# MCU.net
KiCad netlist of a schematic drawn in Altium Designer
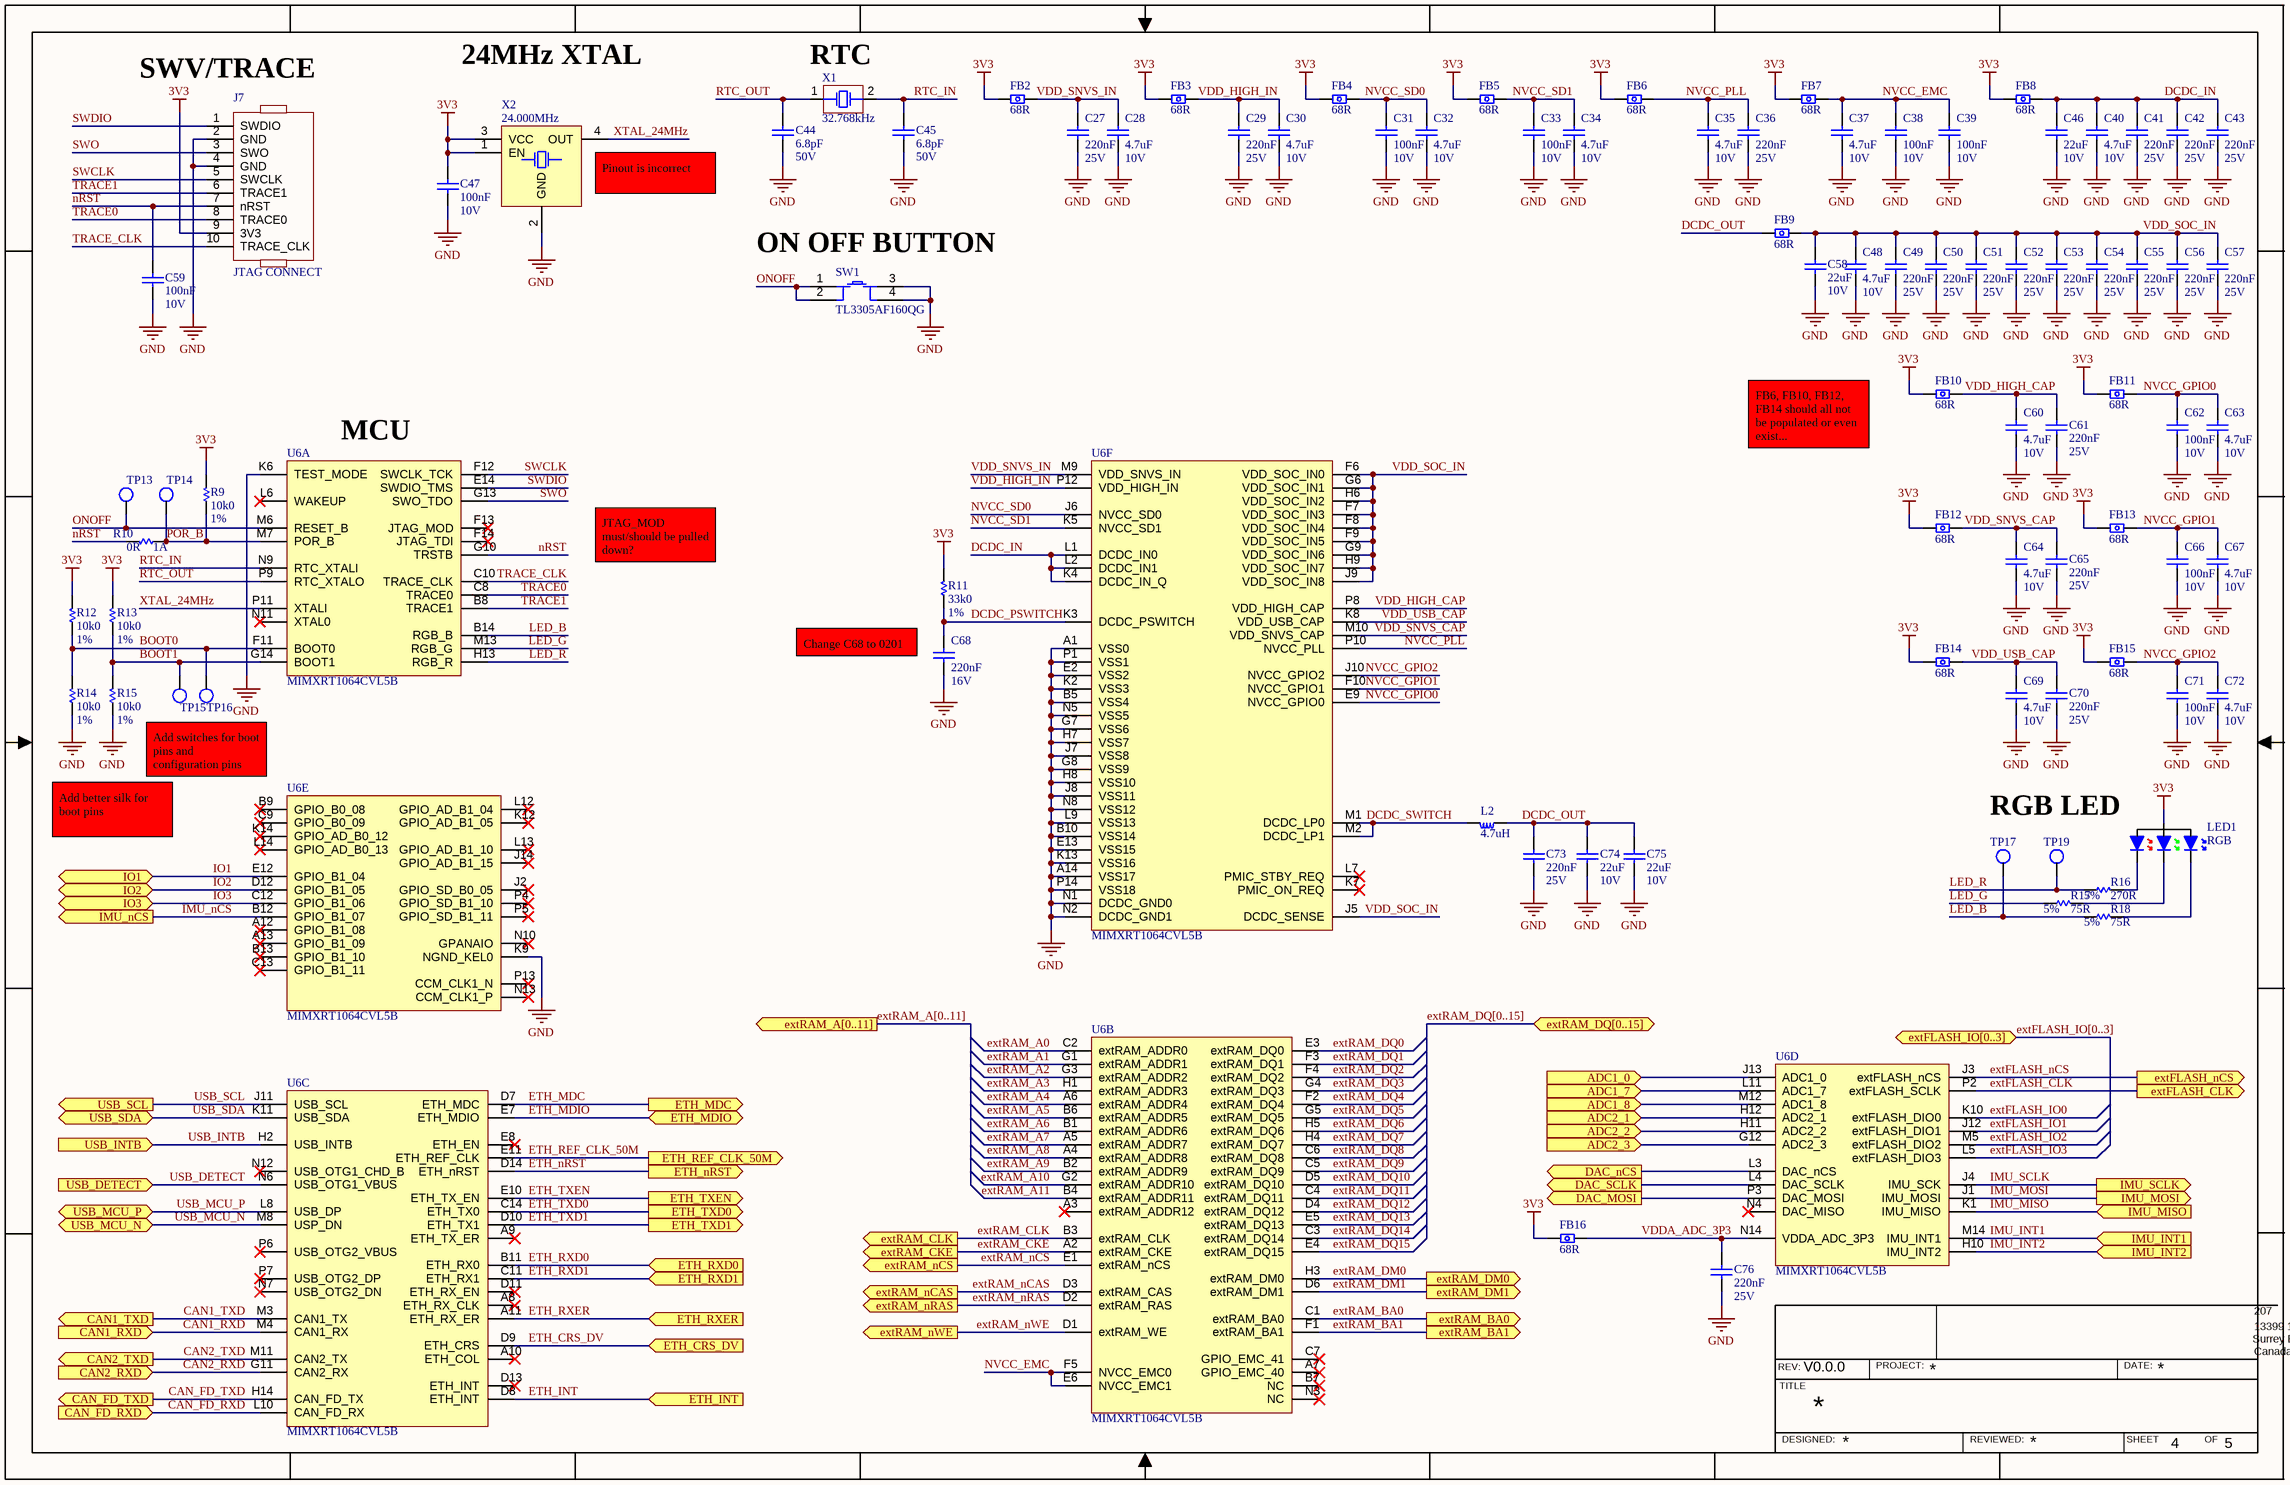
[diagram p0: MCU.SchDoc]

(export (version "E")
  (design (tool "Eeschema 10.0.6"))
  (components
    (comp (ref "C27")
      (value "220nF")
      (footprint "c0201")
      (description "0201 0.22 uF 25 V ±20% Tolerance X5R Surface Mount Multilayer Ceramic Capacitor")
      (fields (field (name "VOLTAGE") "25V"))
      (libsource (lib "MCU") (part "CAP CER 220nF 25V X5R 0201"))
    )
    (comp (ref "C28")
      (value "4.7uF")
      (footprint "C0402")
      (description "0402 10 V 4.7 uF ±20% Tolerance X5R Multilayer Ceramic Chip Capacitor")
      (fields
        (field (name "MANUFACTURER") "Murata")
        (field (name "MANUFACTURER PART NUMBER") "GRM155R61A475MEAAD")
        (field (name "VOLTAGE RATING") "10V")
      )
      (libsource (lib "MCU") (part "CAP CER 4.7uF 10V X5R 0402"))
    )
    (comp (ref "C29")
      (value "220nF")
      (footprint "c0201")
      (description "0201 0.22 uF 25 V ±20% Tolerance X5R Surface Mount Multilayer Ceramic Capacitor")
      (fields (field (name "VOLTAGE") "25V"))
      (libsource (lib "MCU") (part "CAP CER 220nF 25V X5R 0201"))
    )
    (comp (ref "C30")
      (value "4.7uF")
      (footprint "C0402")
      (description "0402 10 V 4.7 uF ±20% Tolerance X5R Multilayer Ceramic Chip Capacitor")
      (fields
        (field (name "MANUFACTURER") "Murata")
        (field (name "MANUFACTURER PART NUMBER") "GRM155R61A475MEAAD")
        (field (name "VOLTAGE RATING") "10V")
      )
      (libsource (lib "MCU") (part "CAP CER 4.7uF 10V X5R 0402"))
    )
    (comp (ref "C31")
      (value "100nF")
      (footprint "C0201")
      (description "CAP CER 0.1UF 10V X5R 0201")
      (fields (field (name "TOLERANCE") "20%") (field (name "VOLTAGE RATING") "10V"))
      (libsource (lib "MCU") (part "CAP CER 100nF 10V X5R 0201"))
    )
    (comp (ref "C32")
      (value "4.7uF")
      (footprint "C0402")
      (description "0402 10 V 4.7 uF ±20% Tolerance X5R Multilayer Ceramic Chip Capacitor")
      (fields
        (field (name "MANUFACTURER") "Murata")
        (field (name "MANUFACTURER PART NUMBER") "GRM155R61A475MEAAD")
        (field (name "VOLTAGE RATING") "10V")
      )
      (libsource (lib "MCU") (part "CAP CER 4.7uF 10V X5R 0402"))
    )
    (comp (ref "C33")
      (value "100nF")
      (footprint "C0201")
      (description "CAP CER 0.1UF 10V X5R 0201")
      (fields (field (name "TOLERANCE") "20%") (field (name "VOLTAGE RATING") "10V"))
      (libsource (lib "MCU") (part "CAP CER 100nF 10V X5R 0201"))
    )
    (comp (ref "C34")
      (value "4.7uF")
      (footprint "C0402")
      (description "0402 10 V 4.7 uF ±20% Tolerance X5R Multilayer Ceramic Chip Capacitor")
      (fields
        (field (name "MANUFACTURER") "Murata")
        (field (name "MANUFACTURER PART NUMBER") "GRM155R61A475MEAAD")
        (field (name "VOLTAGE RATING") "10V")
      )
      (libsource (lib "MCU") (part "CAP CER 4.7uF 10V X5R 0402"))
    )
    (comp (ref "C35")
      (value "4.7uF")
      (footprint "C0402")
      (description "0402 10 V 4.7 uF ±20% Tolerance X5R Multilayer Ceramic Chip Capacitor")
      (fields
        (field (name "MANUFACTURER") "Murata")
        (field (name "MANUFACTURER PART NUMBER") "GRM155R61A475MEAAD")
        (field (name "VOLTAGE RATING") "10V")
      )
      (libsource (lib "MCU") (part "CAP CER 4.7uF 10V X5R 0402"))
    )
    (comp (ref "C36")
      (value "220nF")
      (footprint "c0201")
      (description "0201 0.22 uF 25 V ±20% Tolerance X5R Surface Mount Multilayer Ceramic Capacitor")
      (fields (field (name "VOLTAGE") "25V"))
      (libsource (lib "MCU") (part "CAP CER 220nF 25V X5R 0201"))
    )
    (comp (ref "C37")
      (value "4.7uF")
      (footprint "C0402")
      (description "0402 10 V 4.7 uF ±20% Tolerance X5R Multilayer Ceramic Chip Capacitor")
      (fields
        (field (name "MANUFACTURER") "Murata")
        (field (name "MANUFACTURER PART NUMBER") "GRM155R61A475MEAAD")
        (field (name "VOLTAGE RATING") "10V")
      )
      (libsource (lib "MCU") (part "CAP CER 4.7uF 10V X5R 0402"))
    )
    (comp (ref "C38")
      (value "100nF")
      (footprint "C0201")
      (description "CAP CER 0.1UF 10V X5R 0201")
      (fields (field (name "TOLERANCE") "20%") (field (name "VOLTAGE RATING") "10V"))
      (libsource (lib "MCU") (part "CAP CER 100nF 10V X5R 0201"))
    )
    (comp (ref "C39")
      (value "100nF")
      (footprint "C0201")
      (description "CAP CER 0.1UF 10V X5R 0201")
      (fields (field (name "TOLERANCE") "20%") (field (name "VOLTAGE RATING") "10V"))
      (libsource (lib "MCU") (part "CAP CER 100nF 10V X5R 0201"))
    )
    (comp (ref "C40")
      (value "4.7uF")
      (footprint "C0402")
      (description "0402 10 V 4.7 uF ±20% Tolerance X5R Multilayer Ceramic Chip Capacitor")
      (fields
        (field (name "MANUFACTURER") "Murata")
        (field (name "MANUFACTURER PART NUMBER") "GRM155R61A475MEAAD")
        (field (name "VOLTAGE RATING") "10V")
      )
      (libsource (lib "MCU") (part "CAP CER 4.7uF 10V X5R 0402"))
    )
    (comp (ref "C41")
      (value "220nF")
      (footprint "c0201")
      (description "0201 0.22 uF 25 V ±20% Tolerance X5R Surface Mount Multilayer Ceramic Capacitor")
      (fields (field (name "VOLTAGE") "25V"))
      (libsource (lib "MCU") (part "CAP CER 220nF 25V X5R 0201"))
    )
    (comp (ref "C42")
      (value "220nF")
      (footprint "c0201")
      (description "0201 0.22 uF 25 V ±20% Tolerance X5R Surface Mount Multilayer Ceramic Capacitor")
      (fields (field (name "VOLTAGE") "25V"))
      (libsource (lib "MCU") (part "CAP CER 220nF 25V X5R 0201"))
    )
    (comp (ref "C43")
      (value "220nF")
      (footprint "c0201")
      (description "0201 0.22 uF 25 V ±20% Tolerance X5R Surface Mount Multilayer Ceramic Capacitor")
      (fields (field (name "VOLTAGE") "25V"))
      (libsource (lib "MCU") (part "CAP CER 220nF 25V X5R 0201"))
    )
    (comp (ref "C44")
      (value "6.8pF")
      (footprint "C0402")
      (description "Ceramic capacitor SMD-0402 6, 8pF /50V C0G# C +-0, 25pF%, Samsung, RoHS")
      (fields
        (field (name "MANUFACTURER") "Samsung")
        (field (name "MANUFACTURER PART NUMBER") "CL05C6R8CB5NNNC")
        (field (name "VOLTAGE") "50V")
      )
      (libsource (lib "Control_SchematicLib") (part "CAP CER 6.8pF 50V C0G 0402"))
    )
    (comp (ref "C45")
      (value "6.8pF")
      (footprint "C0402")
      (description "Ceramic capacitor SMD-0402 6, 8pF /50V C0G# C +-0, 25pF%, Samsung, RoHS")
      (fields
        (field (name "MANUFACTURER") "Samsung")
        (field (name "MANUFACTURER PART NUMBER") "CL05C6R8CB5NNNC")
        (field (name "VOLTAGE") "50V")
      )
      (libsource (lib "Control_SchematicLib") (part "CAP CER 6.8pF 50V C0G 0402"))
    )
    (comp (ref "C46")
      (value "22uF")
      (footprint "c0603")
      (description "0603 22 uF 10 V ±20% Tolerance X5R Multilayer Ceramic Chip Capacitor")
      (fields
        (field (name "MANUFACTURER") "Murata")
        (field (name "MANUFACTURER PART NUMBER") "GRM188R61A226ME15D")
        (field (name "VOLTAGE RATING") "10V")
      )
      (libsource (lib "MCU") (part "CAP CER 22uF 10V X5R 0603"))
    )
    (comp (ref "C47")
      (value "100nF")
      (footprint "C0201")
      (description "CAP CER 0.1UF 10V X5R 0201")
      (fields (field (name "TOLERANCE") "20%") (field (name "VOLTAGE RATING") "10V"))
      (libsource (lib "MCU") (part "CAP CER 100nF 10V X5R 0201"))
    )
    (comp (ref "C48")
      (value "4.7uF")
      (footprint "C0402")
      (description "0402 10 V 4.7 uF ±20% Tolerance X5R Multilayer Ceramic Chip Capacitor")
      (fields
        (field (name "MANUFACTURER") "Murata")
        (field (name "MANUFACTURER PART NUMBER") "GRM155R61A475MEAAD")
        (field (name "VOLTAGE RATING") "10V")
      )
      (libsource (lib "MCU") (part "CAP CER 4.7uF 10V X5R 0402"))
    )
    (comp (ref "C49")
      (value "220nF")
      (footprint "c0201")
      (description "0201 0.22 uF 25 V ±20% Tolerance X5R Surface Mount Multilayer Ceramic Capacitor")
      (fields (field (name "VOLTAGE") "25V"))
      (libsource (lib "MCU") (part "CAP CER 220nF 25V X5R 0201"))
    )
    (comp (ref "C50")
      (value "220nF")
      (footprint "c0201")
      (description "0201 0.22 uF 25 V ±20% Tolerance X5R Surface Mount Multilayer Ceramic Capacitor")
      (fields (field (name "VOLTAGE") "25V"))
      (libsource (lib "MCU") (part "CAP CER 220nF 25V X5R 0201"))
    )
    (comp (ref "C51")
      (value "220nF")
      (footprint "c0201")
      (description "0201 0.22 uF 25 V ±20% Tolerance X5R Surface Mount Multilayer Ceramic Capacitor")
      (fields (field (name "VOLTAGE") "25V"))
      (libsource (lib "MCU") (part "CAP CER 220nF 25V X5R 0201"))
    )
    (comp (ref "C52")
      (value "220nF")
      (footprint "c0201")
      (description "0201 0.22 uF 25 V ±20% Tolerance X5R Surface Mount Multilayer Ceramic Capacitor")
      (fields (field (name "VOLTAGE") "25V"))
      (libsource (lib "MCU") (part "CAP CER 220nF 25V X5R 0201"))
    )
    (comp (ref "C53")
      (value "220nF")
      (footprint "c0201")
      (description "0201 0.22 uF 25 V ±20% Tolerance X5R Surface Mount Multilayer Ceramic Capacitor")
      (fields (field (name "VOLTAGE") "25V"))
      (libsource (lib "MCU") (part "CAP CER 220nF 25V X5R 0201"))
    )
    (comp (ref "C54")
      (value "220nF")
      (footprint "c0201")
      (description "0201 0.22 uF 25 V ±20% Tolerance X5R Surface Mount Multilayer Ceramic Capacitor")
      (fields (field (name "VOLTAGE") "25V"))
      (libsource (lib "MCU") (part "CAP CER 220nF 25V X5R 0201"))
    )
    (comp (ref "C55")
      (value "220nF")
      (footprint "c0201")
      (description "0201 0.22 uF 25 V ±20% Tolerance X5R Surface Mount Multilayer Ceramic Capacitor")
      (fields (field (name "VOLTAGE") "25V"))
      (libsource (lib "MCU") (part "CAP CER 220nF 25V X5R 0201"))
    )
    (comp (ref "C56")
      (value "220nF")
      (footprint "c0201")
      (description "0201 0.22 uF 25 V ±20% Tolerance X5R Surface Mount Multilayer Ceramic Capacitor")
      (fields (field (name "VOLTAGE") "25V"))
      (libsource (lib "MCU") (part "CAP CER 220nF 25V X5R 0201"))
    )
    (comp (ref "C57")
      (value "220nF")
      (footprint "c0201")
      (description "0201 0.22 uF 25 V ±20% Tolerance X5R Surface Mount Multilayer Ceramic Capacitor")
      (fields (field (name "VOLTAGE") "25V"))
      (libsource (lib "MCU") (part "CAP CER 220nF 25V X5R 0201"))
    )
    (comp (ref "C58")
      (value "22uF")
      (footprint "c0603")
      (description "0603 22 uF 10 V ±20% Tolerance X5R Multilayer Ceramic Chip Capacitor")
      (fields
        (field (name "MANUFACTURER") "Murata")
        (field (name "MANUFACTURER PART NUMBER") "GRM188R61A226ME15D")
        (field (name "VOLTAGE RATING") "10V")
      )
      (libsource (lib "MCU") (part "CAP CER 22uF 10V X5R 0603"))
    )
    (comp (ref "C59")
      (value "100nF")
      (footprint "C0201")
      (description "CAP CER 0.1UF 10V X5R 0201")
      (fields (field (name "TOLERANCE") "20%") (field (name "VOLTAGE RATING") "10V"))
      (libsource (lib "MCU") (part "CAP CER 100nF 10V X5R 0201"))
    )
    (comp (ref "C60")
      (value "4.7uF")
      (footprint "C0402")
      (description "0402 10 V 4.7 uF ±20% Tolerance X5R Multilayer Ceramic Chip Capacitor")
      (fields
        (field (name "MANUFACTURER") "Murata")
        (field (name "MANUFACTURER PART NUMBER") "GRM155R61A475MEAAD")
        (field (name "VOLTAGE RATING") "10V")
      )
      (libsource (lib "MCU") (part "CAP CER 4.7uF 10V X5R 0402"))
    )
    (comp (ref "C61")
      (value "220nF")
      (footprint "c0201")
      (description "0201 0.22 uF 25 V ±20% Tolerance X5R Surface Mount Multilayer Ceramic Capacitor")
      (fields (field (name "VOLTAGE") "25V"))
      (libsource (lib "MCU") (part "CAP CER 220nF 25V X5R 0201"))
    )
    (comp (ref "C62")
      (value "100nF")
      (footprint "C0201")
      (description "CAP CER 0.1UF 10V X5R 0201")
      (fields (field (name "TOLERANCE") "20%") (field (name "VOLTAGE RATING") "10V"))
      (libsource (lib "MCU") (part "CAP CER 100nF 10V X5R 0201"))
    )
    (comp (ref "C63")
      (value "4.7uF")
      (footprint "C0402")
      (description "0402 10 V 4.7 uF ±20% Tolerance X5R Multilayer Ceramic Chip Capacitor")
      (fields
        (field (name "MANUFACTURER") "Murata")
        (field (name "MANUFACTURER PART NUMBER") "GRM155R61A475MEAAD")
        (field (name "VOLTAGE RATING") "10V")
      )
      (libsource (lib "MCU") (part "CAP CER 4.7uF 10V X5R 0402"))
    )
    (comp (ref "C64")
      (value "4.7uF")
      (footprint "C0402")
      (description "0402 10 V 4.7 uF ±20% Tolerance X5R Multilayer Ceramic Chip Capacitor")
      (fields
        (field (name "MANUFACTURER") "Murata")
        (field (name "MANUFACTURER PART NUMBER") "GRM155R61A475MEAAD")
        (field (name "VOLTAGE RATING") "10V")
      )
      (libsource (lib "MCU") (part "CAP CER 4.7uF 10V X5R 0402"))
    )
    (comp (ref "C65")
      (value "220nF")
      (footprint "c0201")
      (description "0201 0.22 uF 25 V ±20% Tolerance X5R Surface Mount Multilayer Ceramic Capacitor")
      (fields (field (name "VOLTAGE") "25V"))
      (libsource (lib "MCU") (part "CAP CER 220nF 25V X5R 0201"))
    )
    (comp (ref "C66")
      (value "100nF")
      (footprint "C0201")
      (description "CAP CER 0.1UF 10V X5R 0201")
      (fields (field (name "TOLERANCE") "20%") (field (name "VOLTAGE RATING") "10V"))
      (libsource (lib "MCU") (part "CAP CER 100nF 10V X5R 0201"))
    )
    (comp (ref "C67")
      (value "4.7uF")
      (footprint "C0402")
      (description "0402 10 V 4.7 uF ±20% Tolerance X5R Multilayer Ceramic Chip Capacitor")
      (fields
        (field (name "MANUFACTURER") "Murata")
        (field (name "MANUFACTURER PART NUMBER") "GRM155R61A475MEAAD")
        (field (name "VOLTAGE RATING") "10V")
      )
      (libsource (lib "MCU") (part "CAP CER 4.7uF 10V X5R 0402"))
    )
    (comp (ref "C68")
      (value "220nF")
      (footprint "C0402")
      (description "CAP CER 0.22UF 16V X7R 0402")
      (fields
        (field (name "MANUFACTURER") "Samsung")
        (field (name "MANUFACTURER PART NUMBER") "CL05B224KO5NNNC")
        (field (name "VOLTAGE RATING") "16V")
      )
      (libsource (lib "MCU") (part "CAP CER 220nF 16V X7R 0402"))
    )
    (comp (ref "C69")
      (value "4.7uF")
      (footprint "C0402")
      (description "0402 10 V 4.7 uF ±20% Tolerance X5R Multilayer Ceramic Chip Capacitor")
      (fields
        (field (name "MANUFACTURER") "Murata")
        (field (name "MANUFACTURER PART NUMBER") "GRM155R61A475MEAAD")
        (field (name "VOLTAGE RATING") "10V")
      )
      (libsource (lib "MCU") (part "CAP CER 4.7uF 10V X5R 0402"))
    )
    (comp (ref "C70")
      (value "220nF")
      (footprint "c0201")
      (description "0201 0.22 uF 25 V ±20% Tolerance X5R Surface Mount Multilayer Ceramic Capacitor")
      (fields (field (name "VOLTAGE") "25V"))
      (libsource (lib "MCU") (part "CAP CER 220nF 25V X5R 0201"))
    )
    (comp (ref "C71")
      (value "100nF")
      (footprint "C0201")
      (description "CAP CER 0.1UF 10V X5R 0201")
      (fields (field (name "TOLERANCE") "20%") (field (name "VOLTAGE RATING") "10V"))
      (libsource (lib "MCU") (part "CAP CER 100nF 10V X5R 0201"))
    )
    (comp (ref "C72")
      (value "4.7uF")
      (footprint "C0402")
      (description "0402 10 V 4.7 uF ±20% Tolerance X5R Multilayer Ceramic Chip Capacitor")
      (fields
        (field (name "MANUFACTURER") "Murata")
        (field (name "MANUFACTURER PART NUMBER") "GRM155R61A475MEAAD")
        (field (name "VOLTAGE RATING") "10V")
      )
      (libsource (lib "MCU") (part "CAP CER 4.7uF 10V X5R 0402"))
    )
    (comp (ref "C73")
      (value "220nF")
      (footprint "c0201")
      (description "0201 0.22 uF 25 V ±20% Tolerance X5R Surface Mount Multilayer Ceramic Capacitor")
      (fields (field (name "VOLTAGE") "25V"))
      (libsource (lib "MCU") (part "CAP CER 220nF 25V X5R 0201"))
    )
    (comp (ref "C74")
      (value "22uF")
      (footprint "c0603")
      (description "0603 22 uF 10 V ±20% Tolerance X5R Multilayer Ceramic Chip Capacitor")
      (fields
        (field (name "MANUFACTURER") "Murata")
        (field (name "MANUFACTURER PART NUMBER") "GRM188R61A226ME15D")
        (field (name "VOLTAGE RATING") "10V")
      )
      (libsource (lib "MCU") (part "CAP CER 22uF 10V X5R 0603"))
    )
    (comp (ref "C75")
      (value "22uF")
      (footprint "c0603")
      (description "0603 22 uF 10 V ±20% Tolerance X5R Multilayer Ceramic Chip Capacitor")
      (fields
        (field (name "MANUFACTURER") "Murata")
        (field (name "MANUFACTURER PART NUMBER") "GRM188R61A226ME15D")
        (field (name "VOLTAGE RATING") "10V")
      )
      (libsource (lib "MCU") (part "CAP CER 22uF 10V X5R 0603"))
    )
    (comp (ref "C76")
      (value "220nF")
      (footprint "c0201")
      (description "0201 0.22 uF 25 V ±20% Tolerance X5R Surface Mount Multilayer Ceramic Capacitor")
      (fields (field (name "VOLTAGE") "25V"))
      (libsource (lib "MCU") (part "CAP CER 220nF 25V X5R 0201"))
    )
    (comp (ref "FB2")
      (value "68R")
      (footprint "FB0402")
      (description "Ferrite Beads Multi-Layer 68Ohm 25% 100MHz 400mA 310mOhm DCR 0402 T/R")
      (fields
        (field (name "MANUFACTURER") "Taiyo Yuden")
        (field (name "MANUFACTURER PART NUMBER") "BK1005LL680-T")
      )
      (libsource (lib "MCU") (part "FB 68R 400mA 310mR 0402"))
    )
    (comp (ref "FB3")
      (value "68R")
      (footprint "FB0402")
      (description "Ferrite Beads Multi-Layer 68Ohm 25% 100MHz 400mA 310mOhm DCR 0402 T/R")
      (fields
        (field (name "MANUFACTURER") "Taiyo Yuden")
        (field (name "MANUFACTURER PART NUMBER") "BK1005LL680-T")
      )
      (libsource (lib "MCU") (part "FB 68R 400mA 310mR 0402"))
    )
    (comp (ref "FB4")
      (value "68R")
      (footprint "FB0402")
      (description "Ferrite Beads Multi-Layer 68Ohm 25% 100MHz 400mA 310mOhm DCR 0402 T/R")
      (fields
        (field (name "MANUFACTURER") "Taiyo Yuden")
        (field (name "MANUFACTURER PART NUMBER") "BK1005LL680-T")
      )
      (libsource (lib "MCU") (part "FB 68R 400mA 310mR 0402"))
    )
    (comp (ref "FB5")
      (value "68R")
      (footprint "FB0402")
      (description "Ferrite Beads Multi-Layer 68Ohm 25% 100MHz 400mA 310mOhm DCR 0402 T/R")
      (fields
        (field (name "MANUFACTURER") "Taiyo Yuden")
        (field (name "MANUFACTURER PART NUMBER") "BK1005LL680-T")
      )
      (libsource (lib "MCU") (part "FB 68R 400mA 310mR 0402"))
    )
    (comp (ref "FB6")
      (value "68R")
      (footprint "FB0402")
      (description "Ferrite Beads Multi-Layer 68Ohm 25% 100MHz 400mA 310mOhm DCR 0402 T/R")
      (fields
        (field (name "MANUFACTURER") "Taiyo Yuden")
        (field (name "MANUFACTURER PART NUMBER") "BK1005LL680-T")
      )
      (libsource (lib "MCU") (part "FB 68R 400mA 310mR 0402"))
    )
    (comp (ref "FB7")
      (value "68R")
      (footprint "FB0402")
      (description "Ferrite Beads Multi-Layer 68Ohm 25% 100MHz 400mA 310mOhm DCR 0402 T/R")
      (fields
        (field (name "MANUFACTURER") "Taiyo Yuden")
        (field (name "MANUFACTURER PART NUMBER") "BK1005LL680-T")
      )
      (libsource (lib "MCU") (part "FB 68R 400mA 310mR 0402"))
    )
    (comp (ref "FB8")
      (value "68R")
      (footprint "FB0402")
      (description "Ferrite Beads Multi-Layer 68Ohm 25% 100MHz 400mA 310mOhm DCR 0402 T/R")
      (fields
        (field (name "MANUFACTURER") "Taiyo Yuden")
        (field (name "MANUFACTURER PART NUMBER") "BK1005LL680-T")
      )
      (libsource (lib "MCU") (part "FB 68R 400mA 310mR 0402"))
    )
    (comp (ref "FB9")
      (value "68R")
      (footprint "FB0402")
      (description "Ferrite Beads Multi-Layer 68Ohm 25% 100MHz 400mA 310mOhm DCR 0402 T/R")
      (fields
        (field (name "MANUFACTURER") "Taiyo Yuden")
        (field (name "MANUFACTURER PART NUMBER") "BK1005LL680-T")
      )
      (libsource (lib "MCU") (part "FB 68R 400mA 310mR 0402"))
    )
    (comp (ref "FB10")
      (value "68R")
      (footprint "FB0402")
      (description "Ferrite Beads Multi-Layer 68Ohm 25% 100MHz 400mA 310mOhm DCR 0402 T/R")
      (fields
        (field (name "MANUFACTURER") "Taiyo Yuden")
        (field (name "MANUFACTURER PART NUMBER") "BK1005LL680-T")
      )
      (libsource (lib "MCU") (part "FB 68R 400mA 310mR 0402"))
    )
    (comp (ref "FB11")
      (value "68R")
      (footprint "FB0402")
      (description "Ferrite Beads Multi-Layer 68Ohm 25% 100MHz 400mA 310mOhm DCR 0402 T/R")
      (fields
        (field (name "MANUFACTURER") "Taiyo Yuden")
        (field (name "MANUFACTURER PART NUMBER") "BK1005LL680-T")
      )
      (libsource (lib "MCU") (part "FB 68R 400mA 310mR 0402"))
    )
    (comp (ref "FB12")
      (value "68R")
      (footprint "FB0402")
      (description "Ferrite Beads Multi-Layer 68Ohm 25% 100MHz 400mA 310mOhm DCR 0402 T/R")
      (fields
        (field (name "MANUFACTURER") "Taiyo Yuden")
        (field (name "MANUFACTURER PART NUMBER") "BK1005LL680-T")
      )
      (libsource (lib "MCU") (part "FB 68R 400mA 310mR 0402"))
    )
    (comp (ref "FB13")
      (value "68R")
      (footprint "FB0402")
      (description "Ferrite Beads Multi-Layer 68Ohm 25% 100MHz 400mA 310mOhm DCR 0402 T/R")
      (fields
        (field (name "MANUFACTURER") "Taiyo Yuden")
        (field (name "MANUFACTURER PART NUMBER") "BK1005LL680-T")
      )
      (libsource (lib "MCU") (part "FB 68R 400mA 310mR 0402"))
    )
    (comp (ref "FB14")
      (value "68R")
      (footprint "FB0402")
      (description "Ferrite Beads Multi-Layer 68Ohm 25% 100MHz 400mA 310mOhm DCR 0402 T/R")
      (fields
        (field (name "MANUFACTURER") "Taiyo Yuden")
        (field (name "MANUFACTURER PART NUMBER") "BK1005LL680-T")
      )
      (libsource (lib "MCU") (part "FB 68R 400mA 310mR 0402"))
    )
    (comp (ref "FB15")
      (value "68R")
      (footprint "FB0402")
      (description "Ferrite Beads Multi-Layer 68Ohm 25% 100MHz 400mA 310mOhm DCR 0402 T/R")
      (fields
        (field (name "MANUFACTURER") "Taiyo Yuden")
        (field (name "MANUFACTURER PART NUMBER") "BK1005LL680-T")
      )
      (libsource (lib "MCU") (part "FB 68R 400mA 310mR 0402"))
    )
    (comp (ref "FB16")
      (value "68R")
      (footprint "FB0402")
      (description "Ferrite Beads Multi-Layer 68Ohm 25% 100MHz 400mA 310mOhm DCR 0402 T/R")
      (fields
        (field (name "MANUFACTURER") "Taiyo Yuden")
        (field (name "MANUFACTURER PART NUMBER") "BK1005LL680-T")
      )
      (libsource (lib "MCU") (part "FB 68R 400mA 310mR 0402"))
    )
    (comp (ref "J7")
      (value "JTAG CONNECT")
      (footprint "TAG_CONNECT_10PIN")
      (description "10 pin jtag tag connect")
      (libsource (lib "MCU") (part "CONN TAG CONNECT 10 SWV"))
    )
    (comp (ref "L2")
      (value "4.7uH")
      (footprint "INDP3030X12N")
      (description "Inductor Power Shielded Wirewound 4.7uH 20% 100KHz Ferrite 1.06A 0.156Ohm DCR 1212 T/R")
      (fields
        (field (name "MANUFACTURER") "Taiyo Yuden")
        (field (name "MANUFACTURER PART NUMBER") "NRH3012T4R7MN")
      )
      (libsource (lib "MCU") (part "IND 2.7uH 1A 156mR 3030 NRH3012T4R7MN"))
    )
    (comp (ref "LED1")
      (value "RGB")
      (footprint "LED RGB UHD1110-FKA-CL1A13R3Q1BBQFMF3")
      (fields
        (field (name "MANUFACTURER") "Cree")
        (field (name "MANUFACTURER PART NUMBER") "UHD1110-FKA-CL1A13R3Q1BBQFMF3")
      )
      (libsource (lib "Control_SchematicLib") (part "LED RGB 5mA UHD1110-FKA-CL1A13R3Q1BBQFMF3"))
    )
    (comp (ref "R9")
      (value "10k0")
      (footprint "r0402")
      (description "Res General Purpose Thick Film 0402 10K Ohm 1% 1/16W ±100ppm/°C Molded SMD Paper T/R")
      (fields
        (field (name "MANUFACTURER") "Yageo")
        (field (name "MANUFACTURER PART NUMBER") "RC0402FR-0710KL")
        (field (name "TOLERANCE") "1%")
      )
      (libsource (lib "MCU") (part "RES 10k0 1% 63mW 0402"))
    )
    (comp (ref "R10")
      (value "0R")
      (footprint "R0402")
      (description "GLOVE, POLYAMIDE, L/FREE, PU, SIZE 6 - More Details")
      (fields
        (field (name "MANUFACTURER") "Stackpole Electronics")
        (field (name "MANUFACTURER PART NUMBER") "RMCF0402ZT0R00")
        (field (name "CURRENT RATING") "1A")
      )
      (libsource (lib "MCU") (part "RES 0R 63mW 0402"))
    )
    (comp (ref "R11")
      (value "33k0")
      (footprint "r0402")
      (description "Res Thick Film 0402 33K Ohm 1% 0.063W(1/16W) ±100ppm/C Pad SMD T/R")
      (fields
        (field (name "MANUFACTURER") "Samsung")
        (field (name "MANUFACTURER PART NUMBER") "RC1005F333CS")
        (field (name "TOLERANCE") "1%")
      )
      (libsource (lib "MCU") (part "RES 33k0 1% 63mW 0402"))
    )
    (comp (ref "R12")
      (value "10k0")
      (footprint "r0402")
      (description "Res General Purpose Thick Film 0402 10K Ohm 1% 1/16W ±100ppm/°C Molded SMD Paper T/R")
      (fields
        (field (name "MANUFACTURER") "Yageo")
        (field (name "MANUFACTURER PART NUMBER") "RC0402FR-0710KL")
        (field (name "TOLERANCE") "1%")
      )
      (libsource (lib "MCU") (part "RES 10k0 1% 63mW 0402"))
    )
    (comp (ref "R13")
      (value "10k0")
      (footprint "r0402")
      (description "Res General Purpose Thick Film 0402 10K Ohm 1% 1/16W ±100ppm/°C Molded SMD Paper T/R")
      (fields
        (field (name "MANUFACTURER") "Yageo")
        (field (name "MANUFACTURER PART NUMBER") "RC0402FR-0710KL")
        (field (name "TOLERANCE") "1%")
      )
      (libsource (lib "MCU") (part "RES 10k0 1% 63mW 0402"))
    )
    (comp (ref "R14")
      (value "10k0")
      (footprint "r0402")
      (description "Res General Purpose Thick Film 0402 10K Ohm 1% 1/16W ±100ppm/°C Molded SMD Paper T/R")
      (fields
        (field (name "MANUFACTURER") "Yageo")
        (field (name "MANUFACTURER PART NUMBER") "RC0402FR-0710KL")
        (field (name "TOLERANCE") "1%")
      )
      (libsource (lib "MCU") (part "RES 10k0 1% 63mW 0402"))
    )
    (comp (ref "R15")
      (value "10k0")
      (footprint "r0402")
      (description "Res General Purpose Thick Film 0402 10K Ohm 1% 1/16W ±100ppm/°C Molded SMD Paper T/R")
      (fields
        (field (name "MANUFACTURER") "Yageo")
        (field (name "MANUFACTURER PART NUMBER") "RC0402FR-0710KL")
        (field (name "TOLERANCE") "1%")
      )
      (libsource (lib "MCU") (part "RES 10k0 1% 63mW 0402"))
    )
    (comp (ref "R16")
      (value "270R")
      (footprint "r0402")
      (description "Res Thick Film 0402 270 Ohm 5% 0.063W(1/16W) ±100ppm/C Pad SMD Automotive T/R")
      (fields
        (field (name "MANUFACTURER") "Yageo")
        (field (name "MANUFACTURER PART NUMBER") "AC0402JR-07270RL")
        (field (name "TOLERANCE") "5%")
      )
      (libsource (lib "Control_SchematicLib") (part "RES 270R 5% 63mW 0402"))
    )
    (comp (ref "R17")
      (value "75R")
      (footprint "R0402")
      (description "Res Thick Film 0402 75 Ohm 5% 0.063W(1/16W) ±100ppm/C Pad SMD Automotive T/R")
      (fields
        (field (name "MANUFACTURER") "Stackpole Electronics")
        (field (name "MANUFACTURER PART NUMBER") "RMCF0402JT75R0")
        (field (name "TOLERANCE") "5%")
      )
      (libsource (lib "Control_SchematicLib") (part "RES 75R 5% 63mW 0402"))
    )
    (comp (ref "R18")
      (value "75R")
      (footprint "R0402")
      (description "Res Thick Film 0402 75 Ohm 5% 0.063W(1/16W) ±100ppm/C Pad SMD Automotive T/R")
      (fields
        (field (name "MANUFACTURER") "Stackpole Electronics")
        (field (name "MANUFACTURER PART NUMBER") "RMCF0402JT75R0")
        (field (name "TOLERANCE") "5%")
      )
      (libsource (lib "Control_SchematicLib") (part "RES 75R 5% 63mW 0402"))
    )
    (comp (ref "SW1")
      (value "TL3305AF160QG")
      (footprint "MECH PB TL3305A")
      (description "TL3305A Series SPST 12 V 4.5 x 4.5 mm 160 gf Top Actuated SMT Tactile Switch")
      (fields (field (name "MANUFACTURER") "E-Switch"))
      (libsource (lib "MCU") (part "MECH PB SPST TL3305AF160QG"))
    )
    (comp (ref "TP13")
      (value "1mm")
      (footprint "TESTPOINT_SMT")
      (description "SMT testpoint")
      (libsource (lib "DClassAmp_Symbol") (part "TP 1mm"))
    )
    (comp (ref "TP14")
      (value "1mm")
      (footprint "TESTPOINT_SMT")
      (description "SMT testpoint")
      (libsource (lib "DClassAmp_Symbol") (part "TP 1mm"))
    )
    (comp (ref "TP15")
      (value "1mm")
      (footprint "TESTPOINT_SMT")
      (description "SMT testpoint")
      (libsource (lib "DClassAmp_Symbol") (part "TP 1mm"))
    )
    (comp (ref "TP16")
      (value "1mm")
      (footprint "TESTPOINT_SMT")
      (description "SMT testpoint")
      (libsource (lib "DClassAmp_Symbol") (part "TP 1mm"))
    )
    (comp (ref "TP17")
      (value "1mm")
      (footprint "TESTPOINT_SMT")
      (description "SMT testpoint")
      (libsource (lib "DClassAmp_Symbol") (part "TP 1mm"))
    )
    (comp (ref "TP19")
      (value "1mm")
      (footprint "TESTPOINT_SMT")
      (description "SMT testpoint")
      (libsource (lib "DClassAmp_Symbol") (part "TP 1mm"))
    )
    (comp (ref "U6")
      (value "MIMXRT1064CVL5B")
      (footprint "BGA196C65P14X14_1000X1000X143")
      (description "i.MXRT1064 USB Fix 10 / TRAY TRAY MULTIPLE DP BAKEABLE RoHS Compliant: Yes")
      (fields (field (name "MANUFACTURER") "NXP Semiconductors"))
      (libsource (lib "MCU") (part "IC MCU 600MHz LaserDriver MIMXRT1064CVL5B"))
    )
    (comp (ref "X1")
      (value "32.768kHz")
      (footprint "XTAL 3.2x1.5mm")
      (description "Crystal 0.032768MHz ±20ppm (Tol) 12.5pF Flexural 70000Ohm 2-Pin Ultra Mini-CSMD T/R")
      (fields
        (field (name "MANUFACTURER") "ECS International")
        (field (name "MANUFACTURER PART NUMBER") "ECS-.327-12.5-34B-TR")
      )
      (libsource (lib "Control_SchematicLib") (part "XTAL 32.768kHz 20ppm 12.5pF 3.2x1.5mm"))
    )
    (comp (ref "X2")
      (value "24.000MHz")
      (footprint "XTAL FA-238V 3.2x2.5mm")
      (description "Oscillator MEMS 24MHz ±50ppm (Stability) 15pF LVCMOS 55% 3.3V Automotive 4-Pin QFN SMD T/R")
      (fields
        (field (name "MANUFACTURER") "Abracon")
        (field (name "MANUFACTURER PART NUMBER") "ASEM1-24.000MHZ-LC-T")
      )
      (libsource (lib "MCU") (part "XTAL OSC MEMS 24MHz 15pF ASEM1-24.000MHZ-LC-T"))
    )
  )
  (nets
    (net (code "1") (name "/ADC1_0") (class "Default")
      (node (ref "U6") (pin "J13") (pinfunction "ADC1_0_J13") (pintype "passive"))
    )
    (net (code "2") (name "/ADC1_7") (class "Default")
      (node (ref "U6") (pin "L11") (pinfunction "ADC1_7_L11") (pintype "passive"))
    )
    (net (code "3") (name "/ADC1_8") (class "Default")
      (node (ref "U6") (pin "M12") (pinfunction "ADC1_8_M12") (pintype "passive"))
    )
    (net (code "4") (name "/ADC2_1") (class "Default")
      (node (ref "U6") (pin "H12") (pinfunction "ADC2_1_H12") (pintype "passive"))
    )
    (net (code "5") (name "/ADC2_2") (class "Default")
      (node (ref "U6") (pin "H11") (pinfunction "ADC2_2_H11") (pintype "passive"))
    )
    (net (code "6") (name "/ADC2_3") (class "Default")
      (node (ref "U6") (pin "G12") (pinfunction "ADC2_3_G12") (pintype "passive"))
    )
    (net (code "7") (name "/BOOT0") (class "Default")
      (node (ref "R12") (pin "1") (pinfunction "1_1") (pintype "passive"))
      (node (ref "R14") (pin "2") (pinfunction "2_2") (pintype "passive"))
      (node (ref "TP16") (pin "1") (pinfunction "1_1") (pintype "passive"))
      (node (ref "U6") (pin "F11") (pinfunction "BOOT0_F11") (pintype "passive"))
    )
    (net (code "8") (name "/BOOT1") (class "Default")
      (node (ref "R13") (pin "1") (pinfunction "1_1") (pintype "passive"))
      (node (ref "R15") (pin "2") (pinfunction "2_2") (pintype "passive"))
      (node (ref "TP15") (pin "1") (pinfunction "1_1") (pintype "passive"))
      (node (ref "U6") (pin "G14") (pinfunction "BOOT1_G14") (pintype "passive"))
    )
    (net (code "9") (name "/CAN1_RXD") (class "Default")
      (node (ref "U6") (pin "M4") (pinfunction "CAN1_RX_M4") (pintype "passive"))
    )
    (net (code "10") (name "/CAN1_TXD") (class "Default")
      (node (ref "U6") (pin "M3") (pinfunction "CAN1_TX_M3") (pintype "passive"))
    )
    (net (code "11") (name "/CAN2_RXD") (class "Default")
      (node (ref "U6") (pin "G11") (pinfunction "CAN2_RX_G11") (pintype "passive"))
    )
    (net (code "12") (name "/CAN2_TXD") (class "Default")
      (node (ref "U6") (pin "M11") (pinfunction "CAN2_TX_M11") (pintype "passive"))
    )
    (net (code "13") (name "/CAN_FD_RXD") (class "Default")
      (node (ref "U6") (pin "L10") (pinfunction "CAN_FD_RX_L10") (pintype "passive"))
    )
    (net (code "14") (name "/CAN_FD_TXD") (class "Default")
      (node (ref "U6") (pin "H14") (pinfunction "CAN_FD_TX_H14") (pintype "passive"))
    )
    (net (code "15") (name "/DAC_MOSI") (class "Default")
      (node (ref "U6") (pin "P3") (pinfunction "DAC_MOSI_P3") (pintype "passive"))
    )
    (net (code "16") (name "/DAC_SCLK") (class "Default")
      (node (ref "U6") (pin "L4") (pinfunction "DAC_SCLK_L4") (pintype "passive"))
    )
    (net (code "17") (name "/DAC_nCS") (class "Default")
      (node (ref "U6") (pin "L3") (pinfunction "DAC_nCS_L3") (pintype "passive"))
    )
    (net (code "18") (name "/DCDC_IN") (class "Default")
      (node (ref "C40") (pin "2") (pinfunction "2_2") (pintype "passive"))
      (node (ref "C41") (pin "2") (pinfunction "2_2") (pintype "passive"))
      (node (ref "C42") (pin "2") (pinfunction "2_2") (pintype "passive"))
      (node (ref "C43") (pin "2") (pinfunction "2_2") (pintype "passive"))
      (node (ref "C46") (pin "2") (pinfunction "2_2") (pintype "passive"))
      (node (ref "FB8") (pin "1") (pintype "passive"))
      (node (ref "U6") (pin "K4") (pinfunction "DCDC_IN_Q_K4") (pintype "passive"))
      (node (ref "U6") (pin "L1") (pinfunction "DCDC_IN0_L1") (pintype "passive"))
      (node (ref "U6") (pin "L2") (pinfunction "DCDC_IN1_L2") (pintype "passive"))
    )
    (net (code "19") (name "/DCDC_OUT") (class "Default")
      (node (ref "C73") (pin "2") (pinfunction "2_2") (pintype "passive"))
      (node (ref "C74") (pin "2") (pinfunction "2_2") (pintype "passive"))
      (node (ref "C75") (pin "2") (pinfunction "2_2") (pintype "passive"))
      (node (ref "FB9") (pin "2") (pintype "passive"))
      (node (ref "L2") (pin "2") (pinfunction "2_2") (pintype "passive"))
    )
    (net (code "20") (name "/DCDC_PSWITCH") (class "Default")
      (node (ref "C68") (pin "2") (pinfunction "2_2") (pintype "passive"))
      (node (ref "R11") (pin "1") (pinfunction "1_1") (pintype "passive"))
      (node (ref "U6") (pin "K3") (pinfunction "DCDC_PSWITCH_K3") (pintype "passive"))
    )
    (net (code "21") (name "/DCDC_SWITCH") (class "Default")
      (node (ref "L2") (pin "1") (pinfunction "1_1") (pintype "passive"))
      (node (ref "U6") (pin "M1") (pinfunction "DCDC_LP0_M1") (pintype "passive"))
      (node (ref "U6") (pin "M2") (pinfunction "DCDC_LP1_M2") (pintype "passive"))
    )
    (net (code "22") (name "/ETH_CRS_DV") (class "Default")
      (node (ref "U6") (pin "D9") (pinfunction "ETH_CRS_D9") (pintype "passive"))
    )
    (net (code "23") (name "/ETH_INT") (class "Default")
      (node (ref "U6") (pin "D8") (pinfunction "ETH_INT_D8") (pintype "passive"))
    )
    (net (code "24") (name "/ETH_MDC") (class "Default")
      (node (ref "U6") (pin "D7") (pinfunction "ETH_MDC_D7") (pintype "passive"))
    )
    (net (code "25") (name "/ETH_MDIO") (class "Default")
      (node (ref "U6") (pin "E7") (pinfunction "ETH_MDIO_E7") (pintype "passive"))
    )
    (net (code "26") (name "/ETH_REF_CLK_50M") (class "Default")
      (node (ref "U6") (pin "E11") (pinfunction "ETH_REF_CLK_E11") (pintype "passive"))
    )
    (net (code "27") (name "/ETH_RXD0") (class "Default")
      (node (ref "U6") (pin "B11") (pinfunction "ETH_RX0_B11") (pintype "passive"))
    )
    (net (code "28") (name "/ETH_RXD1") (class "Default")
      (node (ref "U6") (pin "C11") (pinfunction "ETH_RX1_C11") (pintype "passive"))
    )
    (net (code "29") (name "/ETH_RXER") (class "Default")
      (node (ref "U6") (pin "A11") (pinfunction "ETH_RX_ER_A11") (pintype "passive"))
    )
    (net (code "30") (name "/ETH_TXD0") (class "Default")
      (node (ref "U6") (pin "C14") (pinfunction "ETH_TX0_C14") (pintype "passive"))
    )
    (net (code "31") (name "/ETH_TXD1") (class "Default")
      (node (ref "U6") (pin "D10") (pinfunction "ETH_TX1_D10") (pintype "passive"))
    )
    (net (code "32") (name "/ETH_TXEN") (class "Default")
      (node (ref "U6") (pin "E10") (pinfunction "ETH_TX_EN_E10") (pintype "passive"))
    )
    (net (code "33") (name "/ETH_nRST") (class "Default")
      (node (ref "U6") (pin "D14") (pinfunction "ETH_nRST_D14") (pintype "passive"))
    )
    (net (code "34") (name "/IMU_INT1") (class "Default")
      (node (ref "U6") (pin "M14") (pinfunction "IMU_INT1_M14") (pintype "passive"))
    )
    (net (code "35") (name "/IMU_INT2") (class "Default")
      (node (ref "U6") (pin "H10") (pinfunction "IMU_INT2_H10") (pintype "passive"))
    )
    (net (code "36") (name "/IMU_MISO") (class "Default")
      (node (ref "U6") (pin "K1") (pinfunction "IMU_MISO_K1") (pintype "passive"))
    )
    (net (code "37") (name "/IMU_MOSI") (class "Default")
      (node (ref "U6") (pin "J1") (pinfunction "IMU_MOSI_J1") (pintype "passive"))
    )
    (net (code "38") (name "/IMU_SCLK") (class "Default")
      (node (ref "U6") (pin "J4") (pinfunction "IMU_SCK_J4") (pintype "passive"))
    )
    (net (code "39") (name "/IMU_nCS") (class "Default")
      (node (ref "U6") (pin "B12") (pinfunction "GPIO_B1_07_B12") (pintype "passive"))
    )
    (net (code "40") (name "/IO1") (class "Default")
      (node (ref "U6") (pin "E12") (pinfunction "GPIO_B1_04_E12") (pintype "passive"))
    )
    (net (code "41") (name "/IO2") (class "Default")
      (node (ref "U6") (pin "D12") (pinfunction "GPIO_B1_05_D12") (pintype "passive"))
    )
    (net (code "42") (name "/IO3") (class "Default")
      (node (ref "U6") (pin "C12") (pinfunction "GPIO_B1_06_C12") (pintype "passive"))
    )
    (net (code "43") (name "/LED_B") (class "Default")
      (node (ref "R18") (pin "1") (pinfunction "1_1") (pintype "passive"))
      (node (ref "TP17") (pin "1") (pinfunction "1_1") (pintype "passive"))
      (node (ref "U6") (pin "B14") (pinfunction "RGB_B_B14") (pintype "passive"))
    )
    (net (code "44") (name "/LED_G") (class "Default")
      (node (ref "R17") (pin "1") (pinfunction "1_1") (pintype "passive"))
      (node (ref "U6") (pin "M13") (pinfunction "RGB_G_M13") (pintype "passive"))
    )
    (net (code "45") (name "/LED_R") (class "Default")
      (node (ref "R16") (pin "1") (pinfunction "1_1") (pintype "passive"))
      (node (ref "TP19") (pin "1") (pinfunction "1_1") (pintype "passive"))
      (node (ref "U6") (pin "H13") (pinfunction "RGB_R_H13") (pintype "passive"))
    )
    (net (code "46") (name "/NVCC_EMC") (class "Default")
      (node (ref "C37") (pin "2") (pinfunction "2_2") (pintype "passive"))
      (node (ref "C38") (pin "2") (pinfunction "2_2") (pintype "passive"))
      (node (ref "C39") (pin "2") (pinfunction "2_2") (pintype "passive"))
      (node (ref "FB7") (pin "1") (pintype "passive"))
      (node (ref "U6") (pin "E6") (pinfunction "NVCC_EMC1_E6") (pintype "passive"))
      (node (ref "U6") (pin "F5") (pinfunction "NVCC_EMC0_F5") (pintype "passive"))
    )
    (net (code "47") (name "/NVCC_GPIO0") (class "Default")
      (node (ref "C62") (pin "2") (pinfunction "2_2") (pintype "passive"))
      (node (ref "C63") (pin "2") (pinfunction "2_2") (pintype "passive"))
      (node (ref "FB11") (pin "1") (pintype "passive"))
      (node (ref "U6") (pin "E9") (pinfunction "NVCC_GPIO0_E9") (pintype "passive"))
    )
    (net (code "48") (name "/NVCC_GPIO1") (class "Default")
      (node (ref "C66") (pin "2") (pinfunction "2_2") (pintype "passive"))
      (node (ref "C67") (pin "2") (pinfunction "2_2") (pintype "passive"))
      (node (ref "FB13") (pin "1") (pintype "passive"))
      (node (ref "U6") (pin "F10") (pinfunction "NVCC_GPIO1_F10") (pintype "passive"))
    )
    (net (code "49") (name "/NVCC_GPIO2") (class "Default")
      (node (ref "C71") (pin "2") (pinfunction "2_2") (pintype "passive"))
      (node (ref "C72") (pin "2") (pinfunction "2_2") (pintype "passive"))
      (node (ref "FB15") (pin "1") (pintype "passive"))
      (node (ref "U6") (pin "J10") (pinfunction "NVCC_GPIO2_J10") (pintype "passive"))
    )
    (net (code "50") (name "/NVCC_PLL") (class "Default")
      (node (ref "C35") (pin "2") (pinfunction "2_2") (pintype "passive"))
      (node (ref "C36") (pin "2") (pinfunction "2_2") (pintype "passive"))
      (node (ref "FB6") (pin "1") (pintype "passive"))
      (node (ref "U6") (pin "P10") (pinfunction "NVCC_PLL_P10") (pintype "passive"))
    )
    (net (code "51") (name "/NVCC_SD0") (class "Default")
      (node (ref "C31") (pin "2") (pinfunction "2_2") (pintype "passive"))
      (node (ref "C32") (pin "2") (pinfunction "2_2") (pintype "passive"))
      (node (ref "FB4") (pin "1") (pintype "passive"))
      (node (ref "U6") (pin "J6") (pinfunction "NVCC_SD0_J6") (pintype "passive"))
    )
    (net (code "52") (name "/NVCC_SD1") (class "Default")
      (node (ref "C33") (pin "2") (pinfunction "2_2") (pintype "passive"))
      (node (ref "C34") (pin "2") (pinfunction "2_2") (pintype "passive"))
      (node (ref "FB5") (pin "1") (pintype "passive"))
      (node (ref "U6") (pin "K5") (pinfunction "NVCC_SD1_K5") (pintype "passive"))
    )
    (net (code "53") (name "/ONOFF") (class "Default")
      (node (ref "SW1") (pin "1") (pinfunction "1_1") (pintype "passive"))
      (node (ref "SW1") (pin "2") (pinfunction "2_2") (pintype "passive"))
      (node (ref "TP13") (pin "1") (pinfunction "1_1") (pintype "passive"))
      (node (ref "U6") (pin "M6") (pinfunction "RESET_B_M6") (pintype "passive"))
    )
    (net (code "54") (name "/POR_B") (class "Default")
      (node (ref "R10") (pin "1") (pinfunction "1_1") (pintype "passive"))
      (node (ref "R9") (pin "1") (pinfunction "1_1") (pintype "passive"))
      (node (ref "TP14") (pin "1") (pinfunction "1_1") (pintype "passive"))
      (node (ref "U6") (pin "M7") (pinfunction "POR_B_M7") (pintype "passive"))
    )
    (net (code "55") (name "/RTC_IN") (class "Default")
      (node (ref "C45") (pin "2") (pinfunction "2_2") (pintype "passive"))
      (node (ref "U6") (pin "N9") (pinfunction "RTC_XTALI_N9") (pintype "passive"))
      (node (ref "X1") (pin "2") (pinfunction "2_2") (pintype "passive"))
    )
    (net (code "56") (name "/RTC_OUT") (class "Default")
      (node (ref "C44") (pin "2") (pinfunction "2_2") (pintype "passive"))
      (node (ref "U6") (pin "P9") (pinfunction "RTC_XTALO_P9") (pintype "passive"))
      (node (ref "X1") (pin "1") (pinfunction "1_1") (pintype "passive"))
    )
    (net (code "57") (name "/SWCLK") (class "Default")
      (node (ref "J7") (pin "5") (pinfunction "SWCLK_5") (pintype "passive"))
      (node (ref "U6") (pin "F12") (pinfunction "SWCLK_TCK_F12") (pintype "passive"))
    )
    (net (code "58") (name "/SWDIO") (class "Default")
      (node (ref "J7") (pin "1") (pinfunction "SWDIO_1") (pintype "passive"))
      (node (ref "U6") (pin "E14") (pinfunction "SWDIO_TMS_E14") (pintype "passive"))
    )
    (net (code "59") (name "/SWO") (class "Default")
      (node (ref "J7") (pin "3") (pinfunction "SWO_3") (pintype "passive"))
      (node (ref "U6") (pin "G13") (pinfunction "SWO_TDO_G13") (pintype "passive"))
    )
    (net (code "60") (name "/TRACE0") (class "Default")
      (node (ref "J7") (pin "8") (pinfunction "TRACE0_8") (pintype "passive"))
      (node (ref "U6") (pin "C8") (pinfunction "TRACE0_C8") (pintype "passive"))
    )
    (net (code "61") (name "/TRACE1") (class "Default")
      (node (ref "J7") (pin "6") (pinfunction "TRACE1_6") (pintype "passive"))
      (node (ref "U6") (pin "B8") (pinfunction "TRACE1_B8") (pintype "passive"))
    )
    (net (code "62") (name "/TRACE_CLK") (class "Default")
      (node (ref "J7") (pin "10") (pinfunction "TRACE_CLK_10") (pintype "passive"))
      (node (ref "U6") (pin "C10") (pinfunction "TRACE_CLK_C10") (pintype "passive"))
    )
    (net (code "63") (name "/USB_DETECT") (class "Default")
      (node (ref "U6") (pin "N6") (pinfunction "USB_OTG1_VBUS_N6") (pintype "passive"))
    )
    (net (code "64") (name "/USB_INTB") (class "Default")
      (node (ref "U6") (pin "H2") (pinfunction "USB_INTB_H2") (pintype "passive"))
    )
    (net (code "65") (name "/USB_MCU_N") (class "Default")
      (node (ref "U6") (pin "M8") (pinfunction "USP_DN_M8") (pintype "passive"))
    )
    (net (code "66") (name "/USB_MCU_P") (class "Default")
      (node (ref "U6") (pin "L8") (pinfunction "USB_DP_L8") (pintype "passive"))
    )
    (net (code "67") (name "/USB_SCL") (class "Default")
      (node (ref "U6") (pin "J11") (pinfunction "USB_SCL_J11") (pintype "passive"))
    )
    (net (code "68") (name "/USB_SDA") (class "Default")
      (node (ref "U6") (pin "K11") (pinfunction "USB_SDA_K11") (pintype "passive"))
    )
    (net (code "69") (name "/VDDA_ADC_3P3") (class "Default")
      (node (ref "C76") (pin "2") (pinfunction "2_2") (pintype "passive"))
      (node (ref "FB16") (pin "1") (pintype "passive"))
      (node (ref "U6") (pin "N14") (pinfunction "VDDA_ADC_3P3_N14") (pintype "passive"))
    )
    (net (code "70") (name "/VDD_HIGH_CAP") (class "Default")
      (node (ref "C60") (pin "2") (pinfunction "2_2") (pintype "passive"))
      (node (ref "C61") (pin "2") (pinfunction "2_2") (pintype "passive"))
      (node (ref "FB10") (pin "1") (pintype "passive"))
      (node (ref "U6") (pin "P8") (pinfunction "VDD_HIGH_CAP_P8") (pintype "passive"))
    )
    (net (code "71") (name "/VDD_HIGH_IN") (class "Default")
      (node (ref "C29") (pin "2") (pinfunction "2_2") (pintype "passive"))
      (node (ref "C30") (pin "2") (pinfunction "2_2") (pintype "passive"))
      (node (ref "FB3") (pin "1") (pintype "passive"))
      (node (ref "U6") (pin "P12") (pinfunction "VDD_HIGH_IN_P12") (pintype "passive"))
    )
    (net (code "72") (name "/VDD_SNVS_CAP") (class "Default")
      (node (ref "C64") (pin "2") (pinfunction "2_2") (pintype "passive"))
      (node (ref "C65") (pin "2") (pinfunction "2_2") (pintype "passive"))
      (node (ref "FB12") (pin "1") (pintype "passive"))
      (node (ref "U6") (pin "M10") (pinfunction "VDD_SNVS_CAP_M10") (pintype "passive"))
    )
    (net (code "73") (name "/VDD_SNVS_IN") (class "Default")
      (node (ref "C27") (pin "2") (pinfunction "2_2") (pintype "passive"))
      (node (ref "C28") (pin "2") (pinfunction "2_2") (pintype "passive"))
      (node (ref "FB2") (pin "1") (pintype "passive"))
      (node (ref "U6") (pin "M9") (pinfunction "VDD_SNVS_IN_M9") (pintype "passive"))
    )
    (net (code "74") (name "/VDD_SOC_IN") (class "Default")
      (node (ref "C48") (pin "2") (pinfunction "2_2") (pintype "passive"))
      (node (ref "C49") (pin "2") (pinfunction "2_2") (pintype "passive"))
      (node (ref "C50") (pin "2") (pinfunction "2_2") (pintype "passive"))
      (node (ref "C51") (pin "2") (pinfunction "2_2") (pintype "passive"))
      (node (ref "C52") (pin "2") (pinfunction "2_2") (pintype "passive"))
      (node (ref "C53") (pin "2") (pinfunction "2_2") (pintype "passive"))
      (node (ref "C54") (pin "2") (pinfunction "2_2") (pintype "passive"))
      (node (ref "C55") (pin "2") (pinfunction "2_2") (pintype "passive"))
      (node (ref "C56") (pin "2") (pinfunction "2_2") (pintype "passive"))
      (node (ref "C57") (pin "2") (pinfunction "2_2") (pintype "passive"))
      (node (ref "C58") (pin "2") (pinfunction "2_2") (pintype "passive"))
      (node (ref "FB9") (pin "1") (pintype "passive"))
      (node (ref "U6") (pin "F6") (pinfunction "VDD_SOC_IN0_F6") (pintype "passive"))
      (node (ref "U6") (pin "F7") (pinfunction "VDD_SOC_IN3_F7") (pintype "passive"))
      (node (ref "U6") (pin "F8") (pinfunction "VDD_SOC_IN4_F8") (pintype "passive"))
      (node (ref "U6") (pin "F9") (pinfunction "VDD_SOC_IN5_F9") (pintype "passive"))
      (node (ref "U6") (pin "G6") (pinfunction "VDD_SOC_IN1_G6") (pintype "passive"))
      (node (ref "U6") (pin "G9") (pinfunction "VDD_SOC_IN6_G9") (pintype "passive"))
      (node (ref "U6") (pin "H6") (pinfunction "VDD_SOC_IN2_H6") (pintype "passive"))
      (node (ref "U6") (pin "H9") (pinfunction "VDD_SOC_IN7_H9") (pintype "passive"))
      (node (ref "U6") (pin "J5") (pinfunction "DCDC_SENSE_J5") (pintype "passive"))
      (node (ref "U6") (pin "J9") (pinfunction "VDD_SOC_IN8_J9") (pintype "passive"))
    )
    (net (code "75") (name "/VDD_USB_CAP") (class "Default")
      (node (ref "C69") (pin "2") (pinfunction "2_2") (pintype "passive"))
      (node (ref "C70") (pin "2") (pinfunction "2_2") (pintype "passive"))
      (node (ref "FB14") (pin "1") (pintype "passive"))
      (node (ref "U6") (pin "K8") (pinfunction "VDD_USB_CAP_K8") (pintype "passive"))
    )
    (net (code "76") (name "/XTAL_24MHz") (class "Default")
      (node (ref "U6") (pin "P11") (pinfunction "XTALI_P11") (pintype "passive"))
      (node (ref "X2") (pin "4") (pinfunction "OUT_4") (pintype "passive"))
    )
    (net (code "77") (name "/extFLASH_CLK") (class "Default")
      (node (ref "U6") (pin "P2") (pinfunction "extFLASH_SCLK_P2") (pintype "passive"))
    )
    (net (code "78") (name "/extFLASH_IO0") (class "Default")
      (node (ref "U6") (pin "K10") (pinfunction "extFLASH_DIO0_K10") (pintype "passive"))
    )
    (net (code "79") (name "/extFLASH_IO1") (class "Default")
      (node (ref "U6") (pin "J12") (pinfunction "extFLASH_DIO1_J12") (pintype "passive"))
    )
    (net (code "80") (name "/extFLASH_IO2") (class "Default")
      (node (ref "U6") (pin "M5") (pinfunction "extFLASH_DIO2_M5") (pintype "passive"))
    )
    (net (code "81") (name "/extFLASH_IO3") (class "Default")
      (node (ref "U6") (pin "L5") (pinfunction "extFLASH_DIO3_L5") (pintype "passive"))
    )
    (net (code "83") (name "/extFLASH_nCS") (class "Default")
      (node (ref "U6") (pin "J3") (pinfunction "extFLASH_nCS_J3") (pintype "passive"))
    )
    (net (code "84") (name "/extRAM_A0") (class "Default")
      (node (ref "U6") (pin "C2") (pinfunction "extRAM_ADDR0_C2") (pintype "passive"))
    )
    (net (code "85") (name "/extRAM_A1") (class "Default")
      (node (ref "U6") (pin "G1") (pinfunction "extRAM_ADDR1_G1") (pintype "passive"))
    )
    (net (code "86") (name "/extRAM_A2") (class "Default")
      (node (ref "U6") (pin "G3") (pinfunction "extRAM_ADDR2_G3") (pintype "passive"))
    )
    (net (code "87") (name "/extRAM_A3") (class "Default")
      (node (ref "U6") (pin "H1") (pinfunction "extRAM_ADDR3_H1") (pintype "passive"))
    )
    (net (code "88") (name "/extRAM_A4") (class "Default")
      (node (ref "U6") (pin "A6") (pinfunction "extRAM_ADDR4_A6") (pintype "passive"))
    )
    (net (code "89") (name "/extRAM_A5") (class "Default")
      (node (ref "U6") (pin "B6") (pinfunction "extRAM_ADDR5_B6") (pintype "passive"))
    )
    (net (code "90") (name "/extRAM_A6") (class "Default")
      (node (ref "U6") (pin "B1") (pinfunction "extRAM_ADDR6_B1") (pintype "passive"))
    )
    (net (code "91") (name "/extRAM_A7") (class "Default")
      (node (ref "U6") (pin "A5") (pinfunction "extRAM_ADDR7_A5") (pintype "passive"))
    )
    (net (code "92") (name "/extRAM_A8") (class "Default")
      (node (ref "U6") (pin "A4") (pinfunction "extRAM_ADDR8_A4") (pintype "passive"))
    )
    (net (code "93") (name "/extRAM_A9") (class "Default")
      (node (ref "U6") (pin "B2") (pinfunction "extRAM_ADDR9_B2") (pintype "passive"))
    )
    (net (code "94") (name "/extRAM_A10") (class "Default")
      (node (ref "U6") (pin "G2") (pinfunction "extRAM_ADDR10_G2") (pintype "passive"))
    )
    (net (code "95") (name "/extRAM_A11") (class "Default")
      (node (ref "U6") (pin "B4") (pinfunction "extRAM_ADDR11_B4") (pintype "passive"))
    )
    (net (code "97") (name "/extRAM_BA0") (class "Default")
      (node (ref "U6") (pin "C1") (pinfunction "extRAM_BA0_C1") (pintype "passive"))
    )
    (net (code "98") (name "/extRAM_BA1") (class "Default")
      (node (ref "U6") (pin "F1") (pinfunction "extRAM_BA1_F1") (pintype "passive"))
    )
    (net (code "99") (name "/extRAM_CKE") (class "Default")
      (node (ref "U6") (pin "A2") (pinfunction "extRAM_CKE_A2") (pintype "passive"))
    )
    (net (code "100") (name "/extRAM_CLK") (class "Default")
      (node (ref "U6") (pin "B3") (pinfunction "extRAM_CLK_B3") (pintype "passive"))
    )
    (net (code "101") (name "/extRAM_DM0") (class "Default")
      (node (ref "U6") (pin "H3") (pinfunction "extRAM_DM0_H3") (pintype "passive"))
    )
    (net (code "102") (name "/extRAM_DM1") (class "Default")
      (node (ref "U6") (pin "D6") (pinfunction "extRAM_DM1_D6") (pintype "passive"))
    )
    (net (code "103") (name "/extRAM_DQ0") (class "Default")
      (node (ref "U6") (pin "E3") (pinfunction "extRAM_DQ0_E3") (pintype "passive"))
    )
    (net (code "104") (name "/extRAM_DQ1") (class "Default")
      (node (ref "U6") (pin "F3") (pinfunction "extRAM_DQ1_F3") (pintype "passive"))
    )
    (net (code "105") (name "/extRAM_DQ2") (class "Default")
      (node (ref "U6") (pin "F4") (pinfunction "extRAM_DQ2_F4") (pintype "passive"))
    )
    (net (code "106") (name "/extRAM_DQ3") (class "Default")
      (node (ref "U6") (pin "G4") (pinfunction "extRAM_DQ3_G4") (pintype "passive"))
    )
    (net (code "107") (name "/extRAM_DQ4") (class "Default")
      (node (ref "U6") (pin "F2") (pinfunction "extRAM_DQ4_F2") (pintype "passive"))
    )
    (net (code "108") (name "/extRAM_DQ5") (class "Default")
      (node (ref "U6") (pin "G5") (pinfunction "extRAM_DQ5_G5") (pintype "passive"))
    )
    (net (code "109") (name "/extRAM_DQ6") (class "Default")
      (node (ref "U6") (pin "H5") (pinfunction "extRAM_DQ6_H5") (pintype "passive"))
    )
    (net (code "110") (name "/extRAM_DQ7") (class "Default")
      (node (ref "U6") (pin "H4") (pinfunction "extRAM_DQ7_H4") (pintype "passive"))
    )
    (net (code "111") (name "/extRAM_DQ8") (class "Default")
      (node (ref "U6") (pin "C6") (pinfunction "extRAM_DQ8_C6") (pintype "passive"))
    )
    (net (code "112") (name "/extRAM_DQ9") (class "Default")
      (node (ref "U6") (pin "C5") (pinfunction "extRAM_DQ9_C5") (pintype "passive"))
    )
    (net (code "113") (name "/extRAM_DQ10") (class "Default")
      (node (ref "U6") (pin "D5") (pinfunction "extRAM_DQ10_D5") (pintype "passive"))
    )
    (net (code "114") (name "/extRAM_DQ11") (class "Default")
      (node (ref "U6") (pin "C4") (pinfunction "extRAM_DQ11_C4") (pintype "passive"))
    )
    (net (code "115") (name "/extRAM_DQ12") (class "Default")
      (node (ref "U6") (pin "D4") (pinfunction "extRAM_DQ12_D4") (pintype "passive"))
    )
    (net (code "116") (name "/extRAM_DQ13") (class "Default")
      (node (ref "U6") (pin "E5") (pinfunction "extRAM_DQ13_E5") (pintype "passive"))
    )
    (net (code "117") (name "/extRAM_DQ14") (class "Default")
      (node (ref "U6") (pin "C3") (pinfunction "extRAM_DQ14_C3") (pintype "passive"))
    )
    (net (code "118") (name "/extRAM_DQ15") (class "Default")
      (node (ref "U6") (pin "E4") (pinfunction "extRAM_DQ15_E4") (pintype "passive"))
    )
    (net (code "120") (name "/extRAM_nCAS") (class "Default")
      (node (ref "U6") (pin "D3") (pinfunction "extRAM_CAS_D3") (pintype "passive"))
    )
    (net (code "121") (name "/extRAM_nCS") (class "Default")
      (node (ref "U6") (pin "E1") (pinfunction "extRAM_nCS_E1") (pintype "passive"))
    )
    (net (code "122") (name "/extRAM_nRAS") (class "Default")
      (node (ref "U6") (pin "D2") (pinfunction "extRAM_RAS_D2") (pintype "passive"))
    )
    (net (code "123") (name "/extRAM_nWE") (class "Default")
      (node (ref "U6") (pin "D1") (pinfunction "extRAM_WE_D1") (pintype "passive"))
    )
    (net (code "124") (name "/nRST") (class "Default")
      (node (ref "C59") (pin "2") (pinfunction "2_2") (pintype "passive"))
      (node (ref "J7") (pin "7") (pinfunction "nRST_7") (pintype "passive"))
      (node (ref "R10") (pin "2") (pinfunction "2_2") (pintype "passive"))
      (node (ref "U6") (pin "G10") (pinfunction "TRSTB_G10") (pintype "passive"))
    )
    (net (code "125") (name "3V3") (class "Default")
      (node (ref "C47") (pin "2") (pinfunction "2_2") (pintype "passive"))
      (node (ref "FB10") (pin "2") (pintype "passive"))
      (node (ref "FB11") (pin "2") (pintype "passive"))
      (node (ref "FB12") (pin "2") (pintype "passive"))
      (node (ref "FB13") (pin "2") (pintype "passive"))
      (node (ref "FB14") (pin "2") (pintype "passive"))
      (node (ref "FB15") (pin "2") (pintype "passive"))
      (node (ref "FB16") (pin "2") (pintype "passive"))
      (node (ref "FB2") (pin "2") (pintype "passive"))
      (node (ref "FB3") (pin "2") (pintype "passive"))
      (node (ref "FB4") (pin "2") (pintype "passive"))
      (node (ref "FB5") (pin "2") (pintype "passive"))
      (node (ref "FB6") (pin "2") (pintype "passive"))
      (node (ref "FB7") (pin "2") (pintype "passive"))
      (node (ref "FB8") (pin "2") (pintype "passive"))
      (node (ref "J7") (pin "9") (pinfunction "3V3_9") (pintype "passive"))
      (node (ref "LED1") (pin "4") (pinfunction "A_4") (pintype "passive"))
      (node (ref "R11") (pin "2") (pinfunction "2_2") (pintype "passive"))
      (node (ref "R12") (pin "2") (pinfunction "2_2") (pintype "passive"))
      (node (ref "R13") (pin "2") (pinfunction "2_2") (pintype "passive"))
      (node (ref "R9") (pin "2") (pinfunction "2_2") (pintype "passive"))
      (node (ref "X2") (pin "1") (pinfunction "EN_1") (pintype "passive"))
      (node (ref "X2") (pin "3") (pinfunction "VCC_3") (pintype "passive"))
    )
    (net (code "126") (name "GND") (class "Default")
      (node (ref "C27") (pin "1") (pinfunction "1_1") (pintype "passive"))
      (node (ref "C28") (pin "1") (pinfunction "1_1") (pintype "passive"))
      (node (ref "C29") (pin "1") (pinfunction "1_1") (pintype "passive"))
      (node (ref "C30") (pin "1") (pinfunction "1_1") (pintype "passive"))
      (node (ref "C31") (pin "1") (pinfunction "1_1") (pintype "passive"))
      (node (ref "C32") (pin "1") (pinfunction "1_1") (pintype "passive"))
      (node (ref "C33") (pin "1") (pinfunction "1_1") (pintype "passive"))
      (node (ref "C34") (pin "1") (pinfunction "1_1") (pintype "passive"))
      (node (ref "C35") (pin "1") (pinfunction "1_1") (pintype "passive"))
      (node (ref "C36") (pin "1") (pinfunction "1_1") (pintype "passive"))
      (node (ref "C37") (pin "1") (pinfunction "1_1") (pintype "passive"))
      (node (ref "C38") (pin "1") (pinfunction "1_1") (pintype "passive"))
      (node (ref "C39") (pin "1") (pinfunction "1_1") (pintype "passive"))
      (node (ref "C40") (pin "1") (pinfunction "1_1") (pintype "passive"))
      (node (ref "C41") (pin "1") (pinfunction "1_1") (pintype "passive"))
      (node (ref "C42") (pin "1") (pinfunction "1_1") (pintype "passive"))
      (node (ref "C43") (pin "1") (pinfunction "1_1") (pintype "passive"))
      (node (ref "C44") (pin "1") (pinfunction "1_1") (pintype "passive"))
      (node (ref "C45") (pin "1") (pinfunction "1_1") (pintype "passive"))
      (node (ref "C46") (pin "1") (pinfunction "1_1") (pintype "passive"))
      (node (ref "C47") (pin "1") (pinfunction "1_1") (pintype "passive"))
      (node (ref "C48") (pin "1") (pinfunction "1_1") (pintype "passive"))
      (node (ref "C49") (pin "1") (pinfunction "1_1") (pintype "passive"))
      (node (ref "C50") (pin "1") (pinfunction "1_1") (pintype "passive"))
      (node (ref "C51") (pin "1") (pinfunction "1_1") (pintype "passive"))
      (node (ref "C52") (pin "1") (pinfunction "1_1") (pintype "passive"))
      (node (ref "C53") (pin "1") (pinfunction "1_1") (pintype "passive"))
      (node (ref "C54") (pin "1") (pinfunction "1_1") (pintype "passive"))
      (node (ref "C55") (pin "1") (pinfunction "1_1") (pintype "passive"))
      (node (ref "C56") (pin "1") (pinfunction "1_1") (pintype "passive"))
      (node (ref "C57") (pin "1") (pinfunction "1_1") (pintype "passive"))
      (node (ref "C58") (pin "1") (pinfunction "1_1") (pintype "passive"))
      (node (ref "C59") (pin "1") (pinfunction "1_1") (pintype "passive"))
      (node (ref "C60") (pin "1") (pinfunction "1_1") (pintype "passive"))
      (node (ref "C61") (pin "1") (pinfunction "1_1") (pintype "passive"))
      (node (ref "C62") (pin "1") (pinfunction "1_1") (pintype "passive"))
      (node (ref "C63") (pin "1") (pinfunction "1_1") (pintype "passive"))
      (node (ref "C64") (pin "1") (pinfunction "1_1") (pintype "passive"))
      (node (ref "C65") (pin "1") (pinfunction "1_1") (pintype "passive"))
      (node (ref "C66") (pin "1") (pinfunction "1_1") (pintype "passive"))
      (node (ref "C67") (pin "1") (pinfunction "1_1") (pintype "passive"))
      (node (ref "C68") (pin "1") (pinfunction "1_1") (pintype "passive"))
      (node (ref "C69") (pin "1") (pinfunction "1_1") (pintype "passive"))
      (node (ref "C70") (pin "1") (pinfunction "1_1") (pintype "passive"))
      (node (ref "C71") (pin "1") (pinfunction "1_1") (pintype "passive"))
      (node (ref "C72") (pin "1") (pinfunction "1_1") (pintype "passive"))
      (node (ref "C73") (pin "1") (pinfunction "1_1") (pintype "passive"))
      (node (ref "C74") (pin "1") (pinfunction "1_1") (pintype "passive"))
      (node (ref "C75") (pin "1") (pinfunction "1_1") (pintype "passive"))
      (node (ref "C76") (pin "1") (pinfunction "1_1") (pintype "passive"))
      (node (ref "J7") (pin "2") (pinfunction "GND_2") (pintype "passive"))
      (node (ref "J7") (pin "4") (pinfunction "GND_4") (pintype "passive"))
      (node (ref "R14") (pin "1") (pinfunction "1_1") (pintype "passive"))
      (node (ref "R15") (pin "1") (pinfunction "1_1") (pintype "passive"))
      (node (ref "SW1") (pin "3") (pinfunction "3_3") (pintype "passive"))
      (node (ref "SW1") (pin "4") (pinfunction "4_4") (pintype "passive"))
      (node (ref "U6") (pin "A1") (pinfunction "VSS0_A1") (pintype "passive"))
      (node (ref "U6") (pin "A14") (pinfunction "VSS17_A14") (pintype "passive"))
      (node (ref "U6") (pin "B10") (pinfunction "VSS14_B10") (pintype "passive"))
      (node (ref "U6") (pin "B5") (pinfunction "VSS4_B5") (pintype "passive"))
      (node (ref "U6") (pin "E13") (pinfunction "VSS15_E13") (pintype "passive"))
      (node (ref "U6") (pin "E2") (pinfunction "VSS2_E2") (pintype "passive"))
      (node (ref "U6") (pin "G7") (pinfunction "VSS6_G7") (pintype "passive"))
      (node (ref "U6") (pin "G8") (pinfunction "VSS9_G8") (pintype "passive"))
      (node (ref "U6") (pin "H7") (pinfunction "VSS7_H7") (pintype "passive"))
      (node (ref "U6") (pin "H8") (pinfunction "VSS10_H8") (pintype "passive"))
      (node (ref "U6") (pin "J7") (pinfunction "VSS8_J7") (pintype "passive"))
      (node (ref "U6") (pin "J8") (pinfunction "VSS11_J8") (pintype "passive"))
      (node (ref "U6") (pin "K13") (pinfunction "VSS16_K13") (pintype "passive"))
      (node (ref "U6") (pin "K2") (pinfunction "VSS3_K2") (pintype "passive"))
      (node (ref "U6") (pin "K6") (pinfunction "TEST_MODE_K6") (pintype "passive"))
      (node (ref "U6") (pin "K9") (pinfunction "NGND_KEL0_K9") (pintype "passive"))
      (node (ref "U6") (pin "L9") (pinfunction "VSS13_L9") (pintype "passive"))
      (node (ref "U6") (pin "N1") (pinfunction "DCDC_GND0_N1") (pintype "passive"))
      (node (ref "U6") (pin "N2") (pinfunction "DCDC_GND1_N2") (pintype "passive"))
      (node (ref "U6") (pin "N5") (pinfunction "VSS5_N5") (pintype "passive"))
      (node (ref "U6") (pin "N8") (pinfunction "VSS12_N8") (pintype "passive"))
      (node (ref "U6") (pin "P1") (pinfunction "VSS1_P1") (pintype "passive"))
      (node (ref "U6") (pin "P14") (pinfunction "VSS18_P14") (pintype "passive"))
      (node (ref "X2") (pin "2") (pinfunction "GND_2") (pintype "passive"))
    )
    (net (code "127") (name "Net-(LED1-K-Pad1)") (class "Default")
      (node (ref "LED1") (pin "1") (pinfunction "K_1") (pintype "passive"))
      (node (ref "R18") (pin "2") (pinfunction "2_2") (pintype "passive"))
    )
    (net (code "128") (name "Net-(LED1-K-Pad2)") (class "Default")
      (node (ref "LED1") (pin "2") (pinfunction "K_2") (pintype "passive"))
      (node (ref "R17") (pin "2") (pinfunction "2_2") (pintype "passive"))
    )
    (net (code "129") (name "Net-(LED1-K-Pad3)") (class "Default")
      (node (ref "LED1") (pin "3") (pinfunction "K_3") (pintype "passive"))
      (node (ref "R16") (pin "2") (pinfunction "2_2") (pintype "passive"))
    )
    (net (code "130") (name "unconnected-(U6A-JTAG_MOD-PadF13)") (class "Default")
      (node (ref "U6") (pin "F13") (pinfunction "JTAG_MOD_F13") (pintype "passive+no_connect"))
    )
    (net (code "131") (name "unconnected-(U6A-JTAG_TDI-PadF14)") (class "Default")
      (node (ref "U6") (pin "F14") (pinfunction "JTAG_TDI_F14") (pintype "passive+no_connect"))
    )
    (net (code "132") (name "unconnected-(U6A-WAKEUP-PadL6)") (class "Default")
      (node (ref "U6") (pin "L6") (pinfunction "WAKEUP_L6") (pintype "passive+no_connect"))
    )
    (net (code "133") (name "unconnected-(U6A-XTAL0-PadN11)") (class "Default")
      (node (ref "U6") (pin "N11") (pinfunction "XTAL0_N11") (pintype "passive+no_connect"))
    )
    (net (code "134") (name "unconnected-(U6B-GPIO_EMC_40-PadA7)") (class "Default")
      (node (ref "U6") (pin "A7") (pinfunction "GPIO_EMC_40_A7") (pintype "passive+no_connect"))
    )
    (net (code "135") (name "unconnected-(U6B-GPIO_EMC_41-PadC7)") (class "Default")
      (node (ref "U6") (pin "C7") (pinfunction "GPIO_EMC_41_C7") (pintype "passive+no_connect"))
    )
    (net (code "136") (name "unconnected-(U6B-NC-PadB7)") (class "Default")
      (node (ref "U6") (pin "B7") (pinfunction "NC_B7") (pintype "passive+no_connect"))
    )
    (net (code "137") (name "unconnected-(U6B-NC-PadN3)") (class "Default")
      (node (ref "U6") (pin "N3") (pinfunction "NC_N3") (pintype "passive+no_connect"))
    )
    (net (code "138") (name "unconnected-(U6B-extRAM_ADDR12-PadA3)") (class "Default")
      (node (ref "U6") (pin "A3") (pinfunction "extRAM_ADDR12_A3") (pintype "passive+no_connect"))
    )
    (net (code "139") (name "unconnected-(U6C-ETH_COL-PadA10)") (class "Default")
      (node (ref "U6") (pin "A10") (pinfunction "ETH_COL_A10") (pintype "passive+no_connect"))
    )
    (net (code "140") (name "unconnected-(U6C-ETH_EN-PadE8)") (class "Default")
      (node (ref "U6") (pin "E8") (pinfunction "ETH_EN_E8") (pintype "passive+no_connect"))
    )
    (net (code "141") (name "unconnected-(U6C-ETH_INT-PadD13)") (class "Default")
      (node (ref "U6") (pin "D13") (pinfunction "ETH_INT_D13") (pintype "passive+no_connect"))
    )
    (net (code "142") (name "unconnected-(U6C-ETH_RX_CLK-PadA8)") (class "Default")
      (node (ref "U6") (pin "A8") (pinfunction "ETH_RX_CLK_A8") (pintype "passive+no_connect"))
    )
    (net (code "143") (name "unconnected-(U6C-ETH_RX_EN-PadD11)") (class "Default")
      (node (ref "U6") (pin "D11") (pinfunction "ETH_RX_EN_D11") (pintype "passive+no_connect"))
    )
    (net (code "144") (name "unconnected-(U6C-ETH_TX_ER-PadA9)") (class "Default")
      (node (ref "U6") (pin "A9") (pinfunction "ETH_TX_ER_A9") (pintype "passive+no_connect"))
    )
    (net (code "145") (name "unconnected-(U6C-USB_OTG1_CHD_B-PadN12)") (class "Default")
      (node (ref "U6") (pin "N12") (pinfunction "USB_OTG1_CHD_B_N12") (pintype "passive+no_connect"))
    )
    (net (code "146") (name "unconnected-(U6C-USB_OTG2_DN-PadN7)") (class "Default")
      (node (ref "U6") (pin "N7") (pinfunction "USB_OTG2_DN_N7") (pintype "passive+no_connect"))
    )
    (net (code "147") (name "unconnected-(U6C-USB_OTG2_DP-PadP7)") (class "Default")
      (node (ref "U6") (pin "P7") (pinfunction "USB_OTG2_DP_P7") (pintype "passive+no_connect"))
    )
    (net (code "148") (name "unconnected-(U6C-USB_OTG2_VBUS-PadP6)") (class "Default")
      (node (ref "U6") (pin "P6") (pinfunction "USB_OTG2_VBUS_P6") (pintype "passive+no_connect"))
    )
    (net (code "149") (name "unconnected-(U6D-DAC_MISO-PadN4)") (class "Default")
      (node (ref "U6") (pin "N4") (pinfunction "DAC_MISO_N4") (pintype "passive+no_connect"))
    )
    (net (code "150") (name "unconnected-(U6E-CCM_CLK1_N-PadP13)") (class "Default")
      (node (ref "U6") (pin "P13") (pinfunction "CCM_CLK1_N_P13") (pintype "passive+no_connect"))
    )
    (net (code "151") (name "unconnected-(U6E-CCM_CLK1_P-PadN13)") (class "Default")
      (node (ref "U6") (pin "N13") (pinfunction "CCM_CLK1_P_N13") (pintype "passive+no_connect"))
    )
    (net (code "152") (name "unconnected-(U6E-GPANAIO-PadN10)") (class "Default")
      (node (ref "U6") (pin "N10") (pinfunction "GPANAIO_N10") (pintype "passive+no_connect"))
    )
    (net (code "153") (name "unconnected-(U6E-GPIO_AD_B0_12-PadK14)") (class "Default")
      (node (ref "U6") (pin "K14") (pinfunction "GPIO_AD_B0_12_K14") (pintype "passive+no_connect"))
    )
    (net (code "154") (name "unconnected-(U6E-GPIO_AD_B0_13-PadL14)") (class "Default")
      (node (ref "U6") (pin "L14") (pinfunction "GPIO_AD_B0_13_L14") (pintype "passive+no_connect"))
    )
    (net (code "155") (name "unconnected-(U6E-GPIO_AD_B1_04-PadL12)") (class "Default")
      (node (ref "U6") (pin "L12") (pinfunction "GPIO_AD_B1_04_L12") (pintype "passive+no_connect"))
    )
    (net (code "156") (name "unconnected-(U6E-GPIO_AD_B1_05-PadK12)") (class "Default")
      (node (ref "U6") (pin "K12") (pinfunction "GPIO_AD_B1_05_K12") (pintype "passive+no_connect"))
    )
    (net (code "157") (name "unconnected-(U6E-GPIO_AD_B1_10-PadL13)") (class "Default")
      (node (ref "U6") (pin "L13") (pinfunction "GPIO_AD_B1_10_L13") (pintype "passive+no_connect"))
    )
    (net (code "158") (name "unconnected-(U6E-GPIO_AD_B1_15-PadJ14)") (class "Default")
      (node (ref "U6") (pin "J14") (pinfunction "GPIO_AD_B1_15_J14") (pintype "passive+no_connect"))
    )
    (net (code "159") (name "unconnected-(U6E-GPIO_B0_08-PadB9)") (class "Default")
      (node (ref "U6") (pin "B9") (pinfunction "GPIO_B0_08_B9") (pintype "passive+no_connect"))
    )
    (net (code "160") (name "unconnected-(U6E-GPIO_B0_09-PadC9)") (class "Default")
      (node (ref "U6") (pin "C9") (pinfunction "GPIO_B0_09_C9") (pintype "passive+no_connect"))
    )
    (net (code "161") (name "unconnected-(U6E-GPIO_B1_08-PadA12)") (class "Default")
      (node (ref "U6") (pin "A12") (pinfunction "GPIO_B1_08_A12") (pintype "passive+no_connect"))
    )
    (net (code "162") (name "unconnected-(U6E-GPIO_B1_09-PadA13)") (class "Default")
      (node (ref "U6") (pin "A13") (pinfunction "GPIO_B1_09_A13") (pintype "passive+no_connect"))
    )
    (net (code "163") (name "unconnected-(U6E-GPIO_B1_10-PadB13)") (class "Default")
      (node (ref "U6") (pin "B13") (pinfunction "GPIO_B1_10_B13") (pintype "passive+no_connect"))
    )
    (net (code "164") (name "unconnected-(U6E-GPIO_B1_11-PadC13)") (class "Default")
      (node (ref "U6") (pin "C13") (pinfunction "GPIO_B1_11_C13") (pintype "passive+no_connect"))
    )
    (net (code "165") (name "unconnected-(U6E-GPIO_SD_B0_05-PadJ2)") (class "Default")
      (node (ref "U6") (pin "J2") (pinfunction "GPIO_SD_B0_05_J2") (pintype "passive+no_connect"))
    )
    (net (code "166") (name "unconnected-(U6E-GPIO_SD_B1_10-PadP4)") (class "Default")
      (node (ref "U6") (pin "P4") (pinfunction "GPIO_SD_B1_10_P4") (pintype "passive+no_connect"))
    )
    (net (code "167") (name "unconnected-(U6E-GPIO_SD_B1_11-PadP5)") (class "Default")
      (node (ref "U6") (pin "P5") (pinfunction "GPIO_SD_B1_11_P5") (pintype "passive+no_connect"))
    )
    (net (code "168") (name "unconnected-(U6F-PMIC_ON_REQ-PadK7)") (class "Default")
      (node (ref "U6") (pin "K7") (pinfunction "PMIC_ON_REQ_K7") (pintype "passive+no_connect"))
    )
    (net (code "169") (name "unconnected-(U6F-PMIC_STBY_REQ-PadL7)") (class "Default")
      (node (ref "U6") (pin "L7") (pinfunction "PMIC_STBY_REQ_L7") (pintype "passive+no_connect"))
    )
  )
)
